# controller.net
KiCad netlist of a schematic drawn in EAGLE
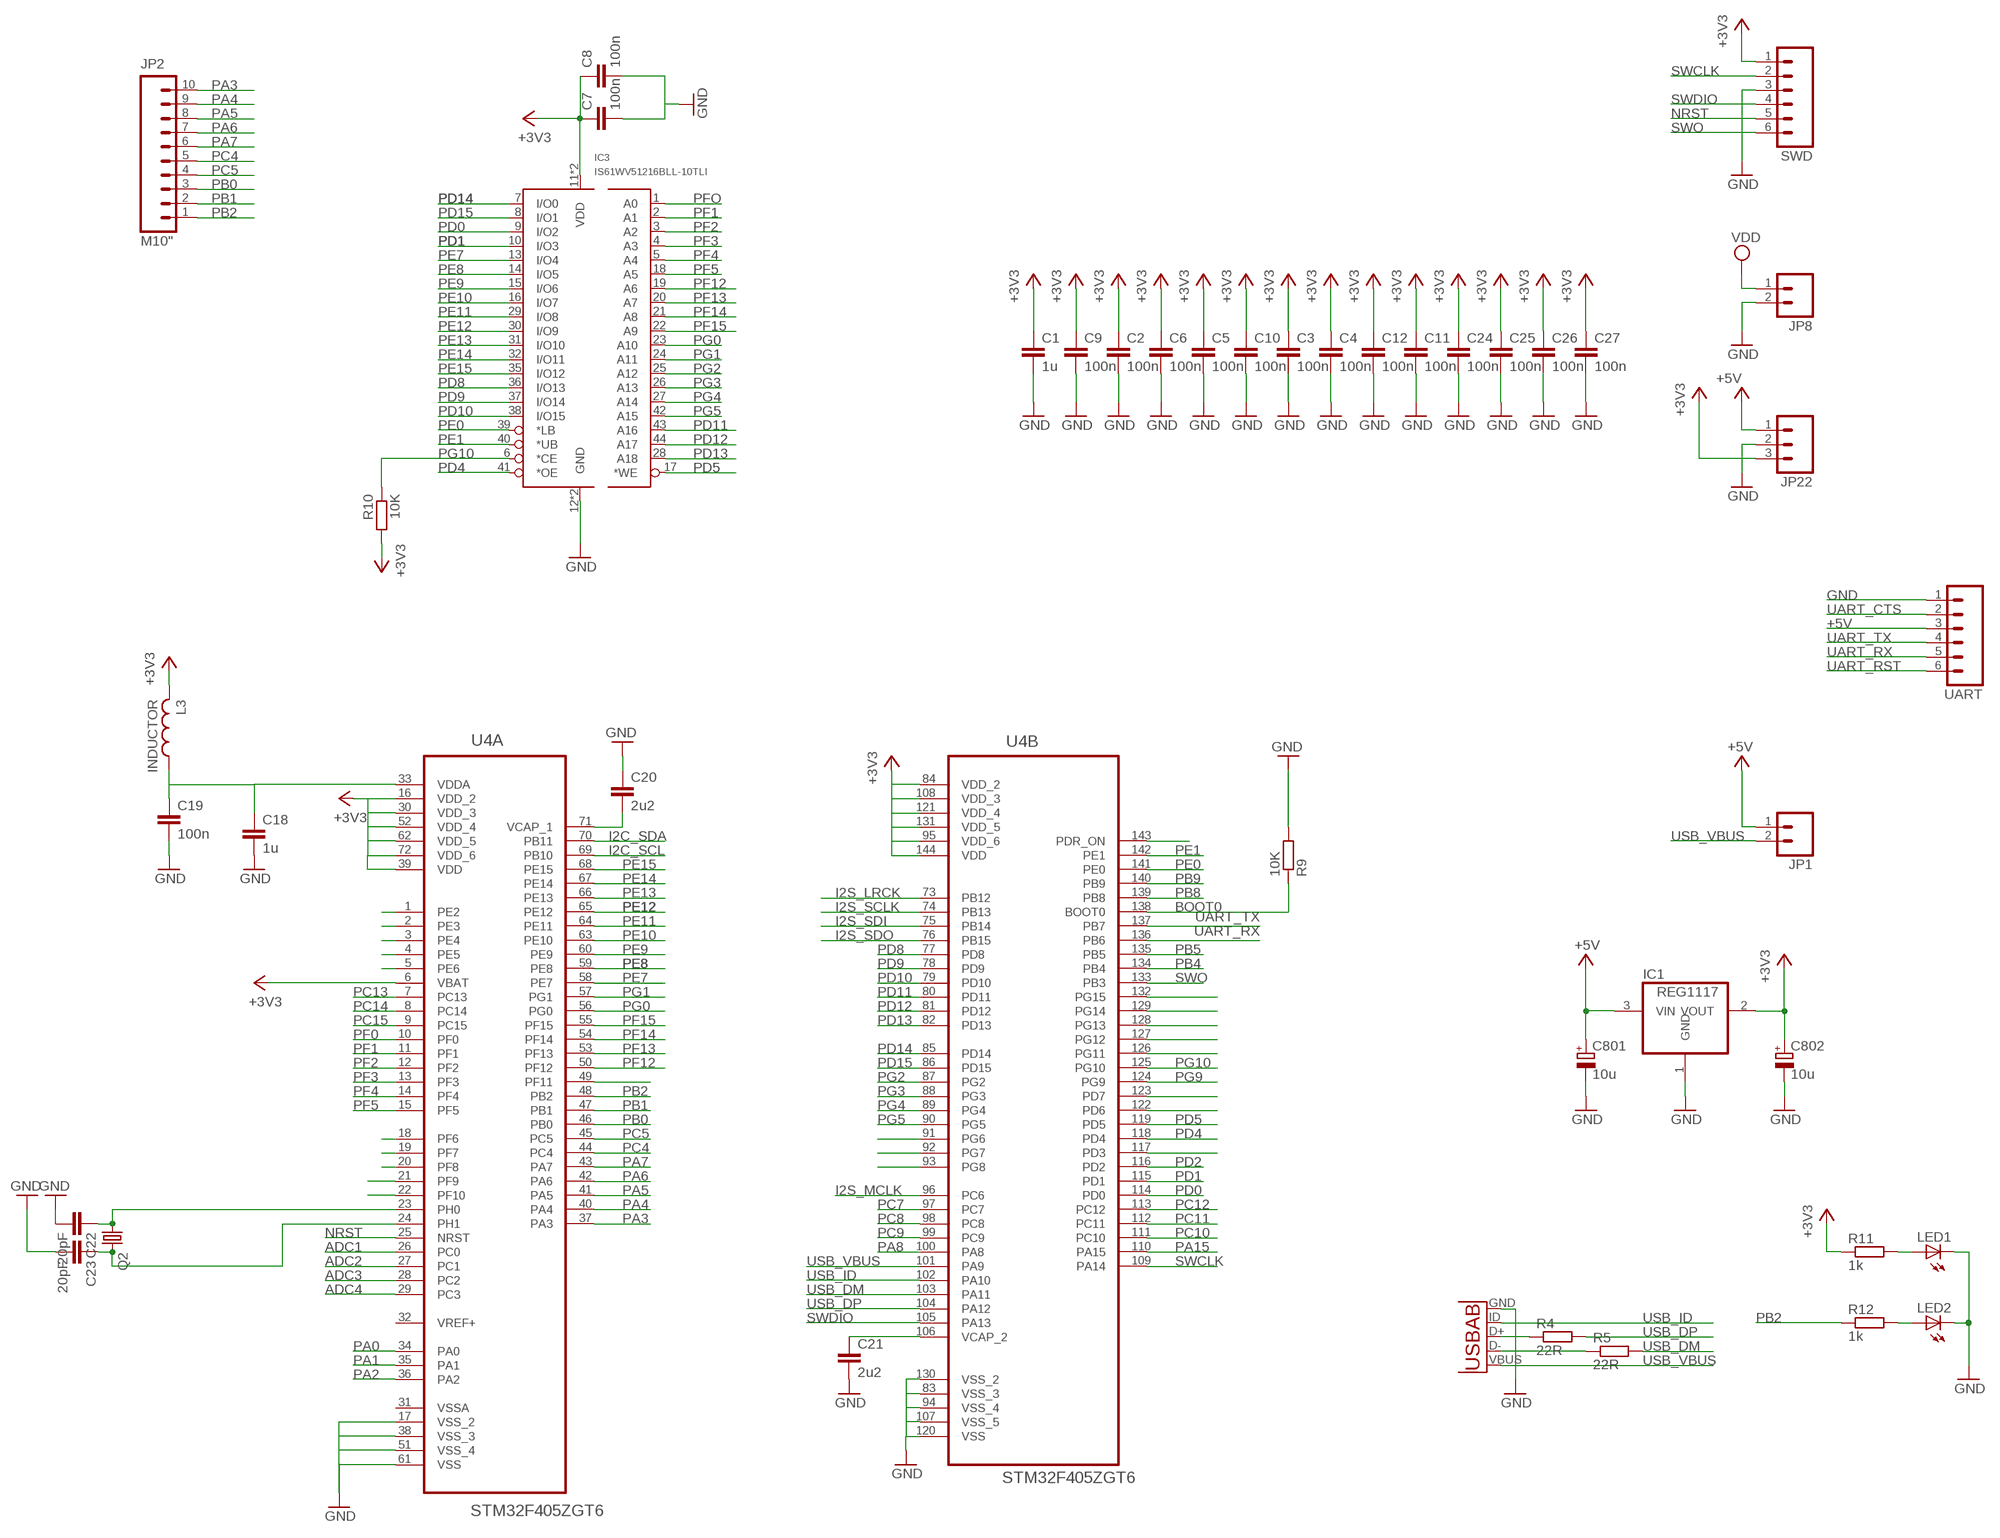
[diagram p0: schematic, sheet 1]

(export (version "E")
  (design (tool "Eeschema 10.0.6"))
  (components
    (comp (ref "C1")
      (value "1u")
      (footprint "eagle-import:C0603")
      (libsource (lib "eagle-import") (part "C-EUC0603"))
    )
    (comp (ref "C2")
      (value "100n")
      (footprint "eagle-import:C0603")
      (libsource (lib "eagle-import") (part "C-EUC0603"))
    )
    (comp (ref "C3")
      (value "100n")
      (footprint "eagle-import:C0603")
      (libsource (lib "eagle-import") (part "C-EUC0603"))
    )
    (comp (ref "C4")
      (value "100n")
      (footprint "eagle-import:C0603")
      (libsource (lib "eagle-import") (part "C-EUC0603"))
    )
    (comp (ref "C5")
      (value "100n")
      (footprint "eagle-import:C0603")
      (libsource (lib "eagle-import") (part "C-EUC0603"))
    )
    (comp (ref "C6")
      (value "100n")
      (footprint "eagle-import:C0603")
      (libsource (lib "eagle-import") (part "C-EUC0603"))
    )
    (comp (ref "C7")
      (value "100n")
      (footprint "eagle-import:C0603")
      (libsource (lib "eagle-import") (part "C-EUC0603"))
    )
    (comp (ref "C8")
      (value "100n")
      (footprint "eagle-import:C0603")
      (libsource (lib "eagle-import") (part "C-EUC0603"))
    )
    (comp (ref "C9")
      (value "100n")
      (footprint "eagle-import:C0603")
      (libsource (lib "eagle-import") (part "C-EUC0603"))
    )
    (comp (ref "C10")
      (value "100n")
      (footprint "eagle-import:C0603")
      (libsource (lib "eagle-import") (part "C-EUC0603"))
    )
    (comp (ref "C11")
      (value "100n")
      (footprint "eagle-import:C0603")
      (libsource (lib "eagle-import") (part "C-EUC0603"))
    )
    (comp (ref "C12")
      (value "100n")
      (footprint "eagle-import:C0603")
      (libsource (lib "eagle-import") (part "C-EUC0603"))
    )
    (comp (ref "C18")
      (value "1u")
      (footprint "eagle-import:C0603")
      (libsource (lib "eagle-import") (part "C-EUC0603"))
    )
    (comp (ref "C19")
      (value "100n")
      (footprint "eagle-import:C0603")
      (libsource (lib "eagle-import") (part "C-EUC0603"))
    )
    (comp (ref "C20")
      (value "2u2")
      (footprint "eagle-import:C0603")
      (libsource (lib "eagle-import") (part "C-EUC0603"))
    )
    (comp (ref "C21")
      (value "2u2")
      (footprint "eagle-import:C0603")
      (libsource (lib "eagle-import") (part "C-EUC0603"))
    )
    (comp (ref "C22")
      (value "20pF")
      (footprint "eagle-import:C0603")
      (libsource (lib "eagle-import") (part "C-EUC0603"))
    )
    (comp (ref "C23")
      (value "20pF")
      (footprint "eagle-import:C0603")
      (libsource (lib "eagle-import") (part "C-EUC0603"))
    )
    (comp (ref "C24")
      (value "100n")
      (footprint "eagle-import:C0603")
      (libsource (lib "eagle-import") (part "C-EUC0603"))
    )
    (comp (ref "C25")
      (value "100n")
      (footprint "eagle-import:C0603")
      (libsource (lib "eagle-import") (part "C-EUC0603"))
    )
    (comp (ref "C26")
      (value "100n")
      (footprint "eagle-import:C0603")
      (libsource (lib "eagle-import") (part "C-EUC0603"))
    )
    (comp (ref "C27")
      (value "100n")
      (footprint "eagle-import:C0603")
      (libsource (lib "eagle-import") (part "C-EUC0603"))
    )
    (comp (ref "C801")
      (value "10u")
      (footprint "eagle-import:PANASONIC_A")
      (libsource (lib "eagle-import") (part "CPOL-EUA"))
    )
    (comp (ref "C802")
      (value "10u")
      (footprint "eagle-import:PANASONIC_A")
      (libsource (lib "eagle-import") (part "CPOL-EUA"))
    )
    (comp (ref "IC1")
      (value "REG1117")
      (footprint "eagle-import:SOT223")
      (libsource (lib "eagle-import") (part "REG1117"))
    )
    (comp (ref "IC3")
      (value "IS61WV51216BLL-10TLI")
      (footprint "eagle-import:TSOP44-II")
      (libsource (lib "eagle-import") (part "IS61WV51216BLL-10TLI"))
    )
    (comp (ref "JP1")
      (value "M02PTH")
      (footprint "eagle-import:1X02")
      (libsource (lib "eagle-import") (part "M02PTH"))
    )
    (comp (ref "JP2")
      (value "M10\"")
      (footprint "eagle-import:1X10")
      (libsource (lib "eagle-import") (part "M10{dblquote}"))
    )
    (comp (ref "JP8")
      (value "M02PTH")
      (footprint "eagle-import:1X02")
      (libsource (lib "eagle-import") (part "M02PTH"))
    )
    (comp (ref "JP22")
      (value "M03PTH")
      (footprint "eagle-import:1X03")
      (libsource (lib "eagle-import") (part "M03PTH"))
    )
    (comp (ref "L3")
      (value "INDUCTOR")
      (footprint "eagle-import:0603")
      (libsource (lib "eagle-import") (part "INDUCTOR"))
    )
    (comp (ref "LED1")
      (value "LED1206")
      (footprint "eagle-import:LED-1206")
      (libsource (lib "eagle-import") (part "LED1206"))
    )
    (comp (ref "LED2")
      (value "LED1206")
      (footprint "eagle-import:LED-1206")
      (libsource (lib "eagle-import") (part "LED1206"))
    )
    (comp (ref "Q2")
      (value "CRYSTALHC49UP")
      (footprint "eagle-import:HC49UP")
      (libsource (lib "eagle-import") (part "CRYSTALHC49UP"))
    )
    (comp (ref "R4")
      (value "22R")
      (footprint "eagle-import:R0603")
      (libsource (lib "eagle-import") (part "R-EU_R0603"))
    )
    (comp (ref "R5")
      (value "22R")
      (footprint "eagle-import:R0603")
      (libsource (lib "eagle-import") (part "R-EU_R0603"))
    )
    (comp (ref "R9")
      (value "10K")
      (footprint "eagle-import:R0603")
      (libsource (lib "eagle-import") (part "R-EU_R0603"))
    )
    (comp (ref "R10")
      (value "10K")
      (footprint "eagle-import:R0603")
      (libsource (lib "eagle-import") (part "R-EU_R0603"))
    )
    (comp (ref "R11")
      (value "1k")
      (footprint "eagle-import:R0603")
      (libsource (lib "eagle-import") (part "R-EU_R0603"))
    )
    (comp (ref "R12")
      (value "1k")
      (footprint "eagle-import:R0603")
      (libsource (lib "eagle-import") (part "R-EU_R0603"))
    )
    (comp (ref "SWD")
      (value "M06SIP")
      (footprint "eagle-import:1X06")
      (libsource (lib "eagle-import") (part "M06SIP"))
    )
    (comp (ref "U3")
      (value "USB-AB")
      (footprint "eagle-import:USB-AB-MICRO-SMD")
      (libsource (lib "eagle-import") (part "USB-AB"))
    )
    (comp (ref "U4")
      (value "STM32F405ZGT6")
      (footprint "eagle-import:QFP50P2200X2200X160-144N")
      (libsource (lib "eagle-import") (part "STM32F405ZGT6"))
    )
    (comp (ref "UART")
      (value "M06SIP")
      (footprint "eagle-import:1X06")
      (libsource (lib "eagle-import") (part "M06SIP"))
    )
  )
  (nets
    (net (code "1") (name "+3V3") (class "Default")
      (node (ref "C1") (pin "1") (pinfunction "1_1") (pintype "passive"))
      (node (ref "C10") (pin "1") (pinfunction "1_1") (pintype "passive"))
      (node (ref "C11") (pin "1") (pinfunction "1_1") (pintype "passive"))
      (node (ref "C12") (pin "1") (pinfunction "1_1") (pintype "passive"))
      (node (ref "C2") (pin "1") (pinfunction "1_1") (pintype "passive"))
      (node (ref "C24") (pin "1") (pinfunction "1_1") (pintype "passive"))
      (node (ref "C25") (pin "1") (pinfunction "1_1") (pintype "passive"))
      (node (ref "C26") (pin "1") (pinfunction "1_1") (pintype "passive"))
      (node (ref "C27") (pin "1") (pinfunction "1_1") (pintype "passive"))
      (node (ref "C3") (pin "1") (pinfunction "1_1") (pintype "passive"))
      (node (ref "C4") (pin "1") (pinfunction "1_1") (pintype "passive"))
      (node (ref "C5") (pin "1") (pinfunction "1_1") (pintype "passive"))
      (node (ref "C6") (pin "1") (pinfunction "1_1") (pintype "passive"))
      (node (ref "C7") (pin "1") (pinfunction "1_1") (pintype "passive"))
      (node (ref "C8") (pin "1") (pinfunction "1_1") (pintype "passive"))
      (node (ref "C802") (pin "+") (pinfunction "+_+") (pintype "passive"))
      (node (ref "C9") (pin "1") (pinfunction "1_1") (pintype "passive"))
      (node (ref "IC1") (pin "2") (pinfunction "VOUT_2") (pintype "output"))
      (node (ref "IC3") (pin "11") (pinfunction "VDD_11") (pintype "power_in"))
      (node (ref "IC3") (pin "33") (pinfunction "VDD_33") (pintype "power_in"))
      (node (ref "JP22") (pin "3") (pinfunction "3_3") (pintype "passive"))
      (node (ref "L3") (pin "2") (pinfunction "2_2") (pintype "passive"))
      (node (ref "R10") (pin "2") (pinfunction "2_2") (pintype "passive"))
      (node (ref "R11") (pin "1") (pinfunction "1_1") (pintype "passive"))
      (node (ref "SWD") (pin "1") (pinfunction "1_1") (pintype "passive"))
      (node (ref "U4") (pin "108") (pinfunction "VDD_3_108") (pintype "power_in"))
      (node (ref "U4") (pin "121") (pinfunction "VDD_4_121") (pintype "power_in"))
      (node (ref "U4") (pin "131") (pinfunction "VDD_5_131") (pintype "power_in"))
      (node (ref "U4") (pin "144") (pinfunction "VDD_144") (pintype "power_in"))
      (node (ref "U4") (pin "16") (pinfunction "VDD_2_16") (pintype "power_in"))
      (node (ref "U4") (pin "30") (pinfunction "VDD_3_30") (pintype "power_in"))
      (node (ref "U4") (pin "39") (pinfunction "VDD_39") (pintype "power_in"))
      (node (ref "U4") (pin "52") (pinfunction "VDD_4_52") (pintype "power_in"))
      (node (ref "U4") (pin "6") (pinfunction "VBAT_6") (pintype "passive"))
      (node (ref "U4") (pin "62") (pinfunction "VDD_5_62") (pintype "power_in"))
      (node (ref "U4") (pin "72") (pinfunction "VDD_6_72") (pintype "power_in"))
      (node (ref "U4") (pin "84") (pinfunction "VDD_2_84") (pintype "power_in"))
      (node (ref "U4") (pin "95") (pinfunction "VDD_6_95") (pintype "power_in"))
    )
    (net (code "2") (name "+5V") (class "Default")
      (node (ref "C801") (pin "+") (pinfunction "+_+") (pintype "passive"))
      (node (ref "IC1") (pin "3") (pinfunction "VIN_3") (pintype "input"))
      (node (ref "JP1") (pin "1") (pinfunction "1_1") (pintype "passive"))
      (node (ref "JP22") (pin "1") (pinfunction "1_1") (pintype "passive"))
      (node (ref "UART") (pin "3") (pinfunction "3_3") (pintype "passive"))
    )
    (net (code "3") (name "/ADC1") (class "Default")
      (node (ref "U4") (pin "26") (pinfunction "PC0_26") (pintype "bidirectional"))
    )
    (net (code "4") (name "/ADC2") (class "Default")
      (node (ref "U4") (pin "27") (pinfunction "PC1_27") (pintype "bidirectional"))
    )
    (net (code "5") (name "/ADC3") (class "Default")
      (node (ref "U4") (pin "28") (pinfunction "PC2_28") (pintype "bidirectional"))
    )
    (net (code "6") (name "/ADC4") (class "Default")
      (node (ref "U4") (pin "29") (pinfunction "PC3_29") (pintype "bidirectional"))
    )
    (net (code "7") (name "/BOOT0") (class "Default")
      (node (ref "R9") (pin "1") (pinfunction "1_1") (pintype "passive"))
      (node (ref "U4") (pin "138") (pinfunction "BOOT0_138") (pintype "passive"))
    )
    (net (code "8") (name "/I2C_SCL") (class "Default")
      (node (ref "U4") (pin "69") (pinfunction "PB10_69") (pintype "bidirectional"))
    )
    (net (code "9") (name "/I2C_SDA") (class "Default")
      (node (ref "U4") (pin "70") (pinfunction "PB11_70") (pintype "bidirectional"))
    )
    (net (code "10") (name "/I2S_LRCK") (class "Default")
      (node (ref "U4") (pin "73") (pinfunction "PB12_73") (pintype "bidirectional"))
    )
    (net (code "11") (name "/I2S_MCLK") (class "Default")
      (node (ref "U4") (pin "96") (pinfunction "PC6_96") (pintype "bidirectional"))
    )
    (net (code "12") (name "/I2S_SCLK") (class "Default")
      (node (ref "U4") (pin "74") (pinfunction "PB13_74") (pintype "bidirectional"))
    )
    (net (code "13") (name "/I2S_SDI") (class "Default")
      (node (ref "U4") (pin "75") (pinfunction "PB14_75") (pintype "bidirectional"))
    )
    (net (code "14") (name "/I2S_SDO") (class "Default")
      (node (ref "U4") (pin "76") (pinfunction "PB15_76") (pintype "bidirectional"))
    )
    (net (code "15") (name "/NRST") (class "Default")
      (node (ref "SWD") (pin "5") (pinfunction "5_5") (pintype "passive"))
      (node (ref "U4") (pin "25") (pinfunction "NRST_25") (pintype "passive"))
    )
    (net (code "16") (name "/PA0") (class "Default")
      (node (ref "U4") (pin "34") (pinfunction "PA0_34") (pintype "bidirectional"))
    )
    (net (code "17") (name "/PA1") (class "Default")
      (node (ref "U4") (pin "35") (pinfunction "PA1_35") (pintype "bidirectional"))
    )
    (net (code "18") (name "/PA2") (class "Default")
      (node (ref "U4") (pin "36") (pinfunction "PA2_36") (pintype "bidirectional"))
    )
    (net (code "19") (name "/PA3") (class "Default")
      (node (ref "JP2") (pin "10") (pinfunction "10_10") (pintype "passive"))
      (node (ref "U4") (pin "37") (pinfunction "PA3_37") (pintype "bidirectional"))
    )
    (net (code "20") (name "/PA4") (class "Default")
      (node (ref "JP2") (pin "9") (pinfunction "9_9") (pintype "passive"))
      (node (ref "U4") (pin "40") (pinfunction "PA4_40") (pintype "bidirectional"))
    )
    (net (code "21") (name "/PA5") (class "Default")
      (node (ref "JP2") (pin "8") (pinfunction "8_8") (pintype "passive"))
      (node (ref "U4") (pin "41") (pinfunction "PA5_41") (pintype "bidirectional"))
    )
    (net (code "22") (name "/PA6") (class "Default")
      (node (ref "JP2") (pin "7") (pinfunction "7_7") (pintype "passive"))
      (node (ref "U4") (pin "42") (pinfunction "PA6_42") (pintype "bidirectional"))
    )
    (net (code "23") (name "/PA7") (class "Default")
      (node (ref "JP2") (pin "6") (pinfunction "6_6") (pintype "passive"))
      (node (ref "U4") (pin "43") (pinfunction "PA7_43") (pintype "bidirectional"))
    )
    (net (code "24") (name "/PA8") (class "Default")
      (node (ref "U4") (pin "100") (pinfunction "PA8_100") (pintype "bidirectional"))
    )
    (net (code "25") (name "/PA15") (class "Default")
      (node (ref "U4") (pin "110") (pinfunction "PA15_110") (pintype "bidirectional"))
    )
    (net (code "26") (name "/PB0") (class "Default")
      (node (ref "JP2") (pin "3") (pinfunction "3_3") (pintype "passive"))
      (node (ref "U4") (pin "46") (pinfunction "PB0_46") (pintype "bidirectional"))
    )
    (net (code "27") (name "/PB1") (class "Default")
      (node (ref "JP2") (pin "2") (pinfunction "2_2") (pintype "passive"))
      (node (ref "U4") (pin "47") (pinfunction "PB1_47") (pintype "bidirectional"))
    )
    (net (code "28") (name "/PB2") (class "Default")
      (node (ref "JP2") (pin "1") (pinfunction "1_1") (pintype "passive"))
      (node (ref "R12") (pin "1") (pinfunction "1_1") (pintype "passive"))
      (node (ref "U4") (pin "48") (pinfunction "PB2_48") (pintype "bidirectional"))
    )
    (net (code "29") (name "/PB4") (class "Default")
      (node (ref "U4") (pin "134") (pinfunction "PB4_134") (pintype "bidirectional"))
    )
    (net (code "30") (name "/PB5") (class "Default")
      (node (ref "U4") (pin "135") (pinfunction "PB5_135") (pintype "bidirectional"))
    )
    (net (code "31") (name "/PB8") (class "Default")
      (node (ref "U4") (pin "139") (pinfunction "PB8_139") (pintype "bidirectional"))
    )
    (net (code "32") (name "/PB9") (class "Default")
      (node (ref "U4") (pin "140") (pinfunction "PB9_140") (pintype "bidirectional"))
    )
    (net (code "33") (name "/PC4") (class "Default")
      (node (ref "JP2") (pin "5") (pinfunction "5_5") (pintype "passive"))
      (node (ref "U4") (pin "44") (pinfunction "PC4_44") (pintype "bidirectional"))
    )
    (net (code "34") (name "/PC5") (class "Default")
      (node (ref "JP2") (pin "4") (pinfunction "4_4") (pintype "passive"))
      (node (ref "U4") (pin "45") (pinfunction "PC5_45") (pintype "bidirectional"))
    )
    (net (code "35") (name "/PC7") (class "Default")
      (node (ref "U4") (pin "97") (pinfunction "PC7_97") (pintype "bidirectional"))
    )
    (net (code "36") (name "/PC8") (class "Default")
      (node (ref "U4") (pin "98") (pinfunction "PC8_98") (pintype "bidirectional"))
    )
    (net (code "37") (name "/PC9") (class "Default")
      (node (ref "U4") (pin "99") (pinfunction "PC9_99") (pintype "bidirectional"))
    )
    (net (code "38") (name "/PC10") (class "Default")
      (node (ref "U4") (pin "111") (pinfunction "PC10_111") (pintype "bidirectional"))
    )
    (net (code "39") (name "/PC11") (class "Default")
      (node (ref "U4") (pin "112") (pinfunction "PC11_112") (pintype "bidirectional"))
    )
    (net (code "40") (name "/PC12") (class "Default")
      (node (ref "U4") (pin "113") (pinfunction "PC12_113") (pintype "bidirectional"))
    )
    (net (code "41") (name "/PC13") (class "Default")
      (node (ref "U4") (pin "7") (pinfunction "PC13_7") (pintype "bidirectional"))
    )
    (net (code "42") (name "/PC14") (class "Default")
      (node (ref "U4") (pin "8") (pinfunction "PC14_8") (pintype "bidirectional"))
    )
    (net (code "43") (name "/PC15") (class "Default")
      (node (ref "U4") (pin "9") (pinfunction "PC15_9") (pintype "bidirectional"))
    )
    (net (code "44") (name "/PD0") (class "Default")
      (node (ref "IC3") (pin "9") (pinfunction "I/O2_9") (pintype "bidirectional"))
      (node (ref "U4") (pin "114") (pinfunction "PD0_114") (pintype "bidirectional"))
    )
    (net (code "45") (name "/PD1") (class "Default")
      (node (ref "IC3") (pin "10") (pinfunction "I/O3_10") (pintype "bidirectional"))
      (node (ref "U4") (pin "115") (pinfunction "PD1_115") (pintype "bidirectional"))
    )
    (net (code "46") (name "/PD2") (class "Default")
      (node (ref "U4") (pin "116") (pinfunction "PD2_116") (pintype "bidirectional"))
    )
    (net (code "47") (name "/PD4") (class "Default")
      (node (ref "IC3") (pin "41") (pinfunction "*OE_41") (pintype "bidirectional"))
      (node (ref "U4") (pin "118") (pinfunction "PD4_118") (pintype "bidirectional"))
    )
    (net (code "48") (name "/PD5") (class "Default")
      (node (ref "IC3") (pin "17") (pinfunction "*WE_17") (pintype "bidirectional"))
      (node (ref "U4") (pin "119") (pinfunction "PD5_119") (pintype "bidirectional"))
    )
    (net (code "49") (name "/PD8") (class "Default")
      (node (ref "IC3") (pin "36") (pinfunction "I/O13_36") (pintype "bidirectional"))
      (node (ref "U4") (pin "77") (pinfunction "PD8_77") (pintype "bidirectional"))
    )
    (net (code "50") (name "/PD9") (class "Default")
      (node (ref "IC3") (pin "37") (pinfunction "I/O14_37") (pintype "bidirectional"))
      (node (ref "U4") (pin "78") (pinfunction "PD9_78") (pintype "bidirectional"))
    )
    (net (code "51") (name "/PD10") (class "Default")
      (node (ref "IC3") (pin "38") (pinfunction "I/O15_38") (pintype "bidirectional"))
      (node (ref "U4") (pin "79") (pinfunction "PD10_79") (pintype "bidirectional"))
    )
    (net (code "52") (name "/PD11") (class "Default")
      (node (ref "IC3") (pin "43") (pinfunction "A16_43") (pintype "input"))
      (node (ref "U4") (pin "80") (pinfunction "PD11_80") (pintype "bidirectional"))
    )
    (net (code "53") (name "/PD12") (class "Default")
      (node (ref "IC3") (pin "44") (pinfunction "A17_44") (pintype "input"))
      (node (ref "U4") (pin "81") (pinfunction "PD12_81") (pintype "bidirectional"))
    )
    (net (code "54") (name "/PD13") (class "Default")
      (node (ref "IC3") (pin "28") (pinfunction "A18_28") (pintype "input"))
      (node (ref "U4") (pin "82") (pinfunction "PD13_82") (pintype "bidirectional"))
    )
    (net (code "55") (name "/PD14") (class "Default")
      (node (ref "IC3") (pin "7") (pinfunction "I/O0_7") (pintype "bidirectional"))
      (node (ref "U4") (pin "85") (pinfunction "PD14_85") (pintype "bidirectional"))
    )
    (net (code "56") (name "/PD15") (class "Default")
      (node (ref "IC3") (pin "8") (pinfunction "I/O1_8") (pintype "bidirectional"))
      (node (ref "U4") (pin "86") (pinfunction "PD15_86") (pintype "bidirectional"))
    )
    (net (code "57") (name "/PE0") (class "Default")
      (node (ref "IC3") (pin "39") (pinfunction "*LB_39") (pintype "bidirectional"))
      (node (ref "U4") (pin "141") (pinfunction "PE0_141") (pintype "bidirectional"))
    )
    (net (code "58") (name "/PE1") (class "Default")
      (node (ref "IC3") (pin "40") (pinfunction "*UB_40") (pintype "bidirectional"))
      (node (ref "U4") (pin "142") (pinfunction "PE1_142") (pintype "bidirectional"))
    )
    (net (code "59") (name "/PE7") (class "Default")
      (node (ref "IC3") (pin "13") (pinfunction "I/O4_13") (pintype "bidirectional"))
      (node (ref "U4") (pin "58") (pinfunction "PE7_58") (pintype "bidirectional"))
    )
    (net (code "60") (name "/PE8") (class "Default")
      (node (ref "IC3") (pin "14") (pinfunction "I/O5_14") (pintype "bidirectional"))
      (node (ref "U4") (pin "59") (pinfunction "PE8_59") (pintype "bidirectional"))
    )
    (net (code "61") (name "/PE9") (class "Default")
      (node (ref "IC3") (pin "15") (pinfunction "I/O6_15") (pintype "bidirectional"))
      (node (ref "U4") (pin "60") (pinfunction "PE9_60") (pintype "bidirectional"))
    )
    (net (code "62") (name "/PE10") (class "Default")
      (node (ref "IC3") (pin "16") (pinfunction "I/O7_16") (pintype "bidirectional"))
      (node (ref "U4") (pin "63") (pinfunction "PE10_63") (pintype "bidirectional"))
    )
    (net (code "63") (name "/PE11") (class "Default")
      (node (ref "IC3") (pin "29") (pinfunction "I/O8_29") (pintype "bidirectional"))
      (node (ref "U4") (pin "64") (pinfunction "PE11_64") (pintype "bidirectional"))
    )
    (net (code "64") (name "/PE12") (class "Default")
      (node (ref "IC3") (pin "30") (pinfunction "I/O9_30") (pintype "bidirectional"))
      (node (ref "U4") (pin "65") (pinfunction "PE12_65") (pintype "bidirectional"))
    )
    (net (code "65") (name "/PE13") (class "Default")
      (node (ref "IC3") (pin "31") (pinfunction "I/O10_31") (pintype "bidirectional"))
      (node (ref "U4") (pin "66") (pinfunction "PE13_66") (pintype "bidirectional"))
    )
    (net (code "66") (name "/PE14") (class "Default")
      (node (ref "IC3") (pin "32") (pinfunction "I/O11_32") (pintype "bidirectional"))
      (node (ref "U4") (pin "67") (pinfunction "PE14_67") (pintype "bidirectional"))
    )
    (net (code "67") (name "/PE15") (class "Default")
      (node (ref "IC3") (pin "35") (pinfunction "I/O12_35") (pintype "bidirectional"))
      (node (ref "U4") (pin "68") (pinfunction "PE15_68") (pintype "bidirectional"))
    )
    (net (code "68") (name "/PF0") (class "Default")
      (node (ref "U4") (pin "10") (pinfunction "PF0_10") (pintype "bidirectional"))
    )
    (net (code "69") (name "/PF1") (class "Default")
      (node (ref "IC3") (pin "2") (pinfunction "A1_2") (pintype "input"))
      (node (ref "U4") (pin "11") (pinfunction "PF1_11") (pintype "bidirectional"))
    )
    (net (code "70") (name "/PF2") (class "Default")
      (node (ref "IC3") (pin "3") (pinfunction "A2_3") (pintype "input"))
      (node (ref "U4") (pin "12") (pinfunction "PF2_12") (pintype "bidirectional"))
    )
    (net (code "71") (name "/PF3") (class "Default")
      (node (ref "IC3") (pin "4") (pinfunction "A3_4") (pintype "input"))
      (node (ref "U4") (pin "13") (pinfunction "PF3_13") (pintype "bidirectional"))
    )
    (net (code "72") (name "/PF4") (class "Default")
      (node (ref "IC3") (pin "5") (pinfunction "A4_5") (pintype "input"))
      (node (ref "U4") (pin "14") (pinfunction "PF4_14") (pintype "bidirectional"))
    )
    (net (code "73") (name "/PF5") (class "Default")
      (node (ref "IC3") (pin "18") (pinfunction "A5_18") (pintype "input"))
      (node (ref "U4") (pin "15") (pinfunction "PF5_15") (pintype "bidirectional"))
    )
    (net (code "74") (name "/PF12") (class "Default")
      (node (ref "IC3") (pin "19") (pinfunction "A6_19") (pintype "input"))
      (node (ref "U4") (pin "50") (pinfunction "PF12_50") (pintype "bidirectional"))
    )
    (net (code "75") (name "/PF13") (class "Default")
      (node (ref "IC3") (pin "20") (pinfunction "A7_20") (pintype "input"))
      (node (ref "U4") (pin "53") (pinfunction "PF13_53") (pintype "bidirectional"))
    )
    (net (code "76") (name "/PF14") (class "Default")
      (node (ref "IC3") (pin "21") (pinfunction "A8_21") (pintype "input"))
      (node (ref "U4") (pin "54") (pinfunction "PF14_54") (pintype "bidirectional"))
    )
    (net (code "77") (name "/PF15") (class "Default")
      (node (ref "IC3") (pin "22") (pinfunction "A9_22") (pintype "input"))
      (node (ref "U4") (pin "55") (pinfunction "PF15_55") (pintype "bidirectional"))
    )
    (net (code "78") (name "/PFO") (class "Default")
      (node (ref "IC3") (pin "1") (pinfunction "A0_1") (pintype "input"))
    )
    (net (code "79") (name "/PG0") (class "Default")
      (node (ref "IC3") (pin "23") (pinfunction "A10_23") (pintype "input"))
      (node (ref "U4") (pin "56") (pinfunction "PG0_56") (pintype "bidirectional"))
    )
    (net (code "80") (name "/PG1") (class "Default")
      (node (ref "IC3") (pin "24") (pinfunction "A11_24") (pintype "input"))
      (node (ref "U4") (pin "57") (pinfunction "PG1_57") (pintype "bidirectional"))
    )
    (net (code "81") (name "/PG2") (class "Default")
      (node (ref "IC3") (pin "25") (pinfunction "A12_25") (pintype "input"))
      (node (ref "U4") (pin "87") (pinfunction "PG2_87") (pintype "bidirectional"))
    )
    (net (code "82") (name "/PG3") (class "Default")
      (node (ref "IC3") (pin "26") (pinfunction "A13_26") (pintype "input"))
      (node (ref "U4") (pin "88") (pinfunction "PG3_88") (pintype "bidirectional"))
    )
    (net (code "83") (name "/PG4") (class "Default")
      (node (ref "IC3") (pin "27") (pinfunction "A14_27") (pintype "input"))
      (node (ref "U4") (pin "89") (pinfunction "PG4_89") (pintype "bidirectional"))
    )
    (net (code "84") (name "/PG5") (class "Default")
      (node (ref "IC3") (pin "42") (pinfunction "A15_42") (pintype "input"))
      (node (ref "U4") (pin "90") (pinfunction "PG5_90") (pintype "bidirectional"))
    )
    (net (code "85") (name "/PG9") (class "Default")
      (node (ref "U4") (pin "124") (pinfunction "PG9_124") (pintype "bidirectional"))
    )
    (net (code "86") (name "/PG10") (class "Default")
      (node (ref "IC3") (pin "6") (pinfunction "*CE_6") (pintype "bidirectional"))
      (node (ref "R10") (pin "1") (pinfunction "1_1") (pintype "passive"))
      (node (ref "U4") (pin "125") (pinfunction "PG10_125") (pintype "bidirectional"))
    )
    (net (code "87") (name "/SWCLK") (class "Default")
      (node (ref "SWD") (pin "2") (pinfunction "2_2") (pintype "passive"))
      (node (ref "U4") (pin "109") (pinfunction "PA14_109") (pintype "bidirectional"))
    )
    (net (code "88") (name "/SWDIO") (class "Default")
      (node (ref "SWD") (pin "4") (pinfunction "4_4") (pintype "passive"))
      (node (ref "U4") (pin "105") (pinfunction "PA13_105") (pintype "bidirectional"))
    )
    (net (code "89") (name "/SWO") (class "Default")
      (node (ref "SWD") (pin "6") (pinfunction "6_6") (pintype "passive"))
      (node (ref "U4") (pin "133") (pinfunction "PB3_133") (pintype "bidirectional"))
    )
    (net (code "90") (name "/UART_CTS") (class "Default")
      (node (ref "UART") (pin "2") (pinfunction "2_2") (pintype "passive"))
    )
    (net (code "91") (name "/UART_RST") (class "Default")
      (node (ref "UART") (pin "6") (pinfunction "6_6") (pintype "passive"))
    )
    (net (code "92") (name "/UART_RX") (class "Default")
      (node (ref "U4") (pin "136") (pinfunction "PB6_136") (pintype "bidirectional"))
      (node (ref "UART") (pin "5") (pinfunction "5_5") (pintype "passive"))
    )
    (net (code "93") (name "/UART_TX") (class "Default")
      (node (ref "U4") (pin "137") (pinfunction "PB7_137") (pintype "bidirectional"))
      (node (ref "UART") (pin "4") (pinfunction "4_4") (pintype "passive"))
    )
    (net (code "94") (name "/USB_DM") (class "Default")
      (node (ref "R5") (pin "2") (pinfunction "2_2") (pintype "passive"))
      (node (ref "U4") (pin "103") (pinfunction "PA11_103") (pintype "bidirectional"))
    )
    (net (code "95") (name "/USB_DP") (class "Default")
      (node (ref "R4") (pin "2") (pinfunction "2_2") (pintype "passive"))
      (node (ref "U4") (pin "104") (pinfunction "PA12_104") (pintype "bidirectional"))
    )
    (net (code "96") (name "/USB_ID") (class "Default")
      (node (ref "U3") (pin "ID") (pinfunction "USBID_ID") (pintype "bidirectional"))
      (node (ref "U4") (pin "102") (pinfunction "PA10_102") (pintype "bidirectional"))
    )
    (net (code "97") (name "/USB_VBUS") (class "Default")
      (node (ref "JP1") (pin "2") (pinfunction "2_2") (pintype "passive"))
      (node (ref "U3") (pin "VBUS") (pinfunction "VBUS_VBUS") (pintype "bidirectional"))
      (node (ref "U4") (pin "101") (pinfunction "PA9_101") (pintype "bidirectional"))
    )
    (net (code "98") (name "/VSSA") (class "Default")
      (node (ref "U4") (pin "31") (pinfunction "VSSA_31") (pintype "power_in"))
    )
    (net (code "99") (name "GND") (class "Default")
      (node (ref "C1") (pin "2") (pinfunction "2_2") (pintype "passive"))
      (node (ref "C10") (pin "2") (pinfunction "2_2") (pintype "passive"))
      (node (ref "C11") (pin "2") (pinfunction "2_2") (pintype "passive"))
      (node (ref "C12") (pin "2") (pinfunction "2_2") (pintype "passive"))
      (node (ref "C18") (pin "2") (pinfunction "2_2") (pintype "passive"))
      (node (ref "C19") (pin "2") (pinfunction "2_2") (pintype "passive"))
      (node (ref "C2") (pin "2") (pinfunction "2_2") (pintype "passive"))
      (node (ref "C20") (pin "1") (pinfunction "1_1") (pintype "passive"))
      (node (ref "C21") (pin "2") (pinfunction "2_2") (pintype "passive"))
      (node (ref "C22") (pin "2") (pinfunction "2_2") (pintype "passive"))
      (node (ref "C23") (pin "2") (pinfunction "2_2") (pintype "passive"))
      (node (ref "C24") (pin "2") (pinfunction "2_2") (pintype "passive"))
      (node (ref "C25") (pin "2") (pinfunction "2_2") (pintype "passive"))
      (node (ref "C26") (pin "2") (pinfunction "2_2") (pintype "passive"))
      (node (ref "C27") (pin "2") (pinfunction "2_2") (pintype "passive"))
      (node (ref "C3") (pin "2") (pinfunction "2_2") (pintype "passive"))
      (node (ref "C4") (pin "2") (pinfunction "2_2") (pintype "passive"))
      (node (ref "C5") (pin "2") (pinfunction "2_2") (pintype "passive"))
      (node (ref "C6") (pin "2") (pinfunction "2_2") (pintype "passive"))
      (node (ref "C7") (pin "2") (pinfunction "2_2") (pintype "passive"))
      (node (ref "C8") (pin "2") (pinfunction "2_2") (pintype "passive"))
      (node (ref "C801") (pin "-") (pinfunction "-_-") (pintype "passive"))
      (node (ref "C802") (pin "-") (pinfunction "-_-") (pintype "passive"))
      (node (ref "C9") (pin "2") (pinfunction "2_2") (pintype "passive"))
      (node (ref "IC1") (pin "1") (pinfunction "GND_1") (pintype "power_in"))
      (node (ref "IC3") (pin "12") (pinfunction "GND_12") (pintype "power_in"))
      (node (ref "IC3") (pin "34") (pinfunction "GND_34") (pintype "power_in"))
      (node (ref "JP22") (pin "2") (pinfunction "2_2") (pintype "passive"))
      (node (ref "JP8") (pin "2") (pinfunction "2_2") (pintype "passive"))
      (node (ref "LED1") (pin "C") (pinfunction "C_C") (pintype "passive"))
      (node (ref "LED2") (pin "C") (pinfunction "C_C") (pintype "passive"))
      (node (ref "R9") (pin "2") (pinfunction "2_2") (pintype "passive"))
      (node (ref "SWD") (pin "3") (pinfunction "3_3") (pintype "passive"))
      (node (ref "U3") (pin "GND") (pinfunction "GND_GND") (pintype "bidirectional"))
      (node (ref "U4") (pin "107") (pinfunction "VSS_5_107") (pintype "power_in"))
      (node (ref "U4") (pin "120") (pinfunction "VSS_120") (pintype "power_in"))
      (node (ref "U4") (pin "130") (pinfunction "VSS_2_130") (pintype "power_in"))
      (node (ref "U4") (pin "17") (pinfunction "VSS_2_17") (pintype "power_in"))
      (node (ref "U4") (pin "38") (pinfunction "VSS_3_38") (pintype "power_in"))
      (node (ref "U4") (pin "51") (pinfunction "VSS_4_51") (pintype "power_in"))
      (node (ref "U4") (pin "61") (pinfunction "VSS_61") (pintype "power_in"))
      (node (ref "U4") (pin "83") (pinfunction "VSS_3_83") (pintype "power_in"))
      (node (ref "U4") (pin "94") (pinfunction "VSS_4_94") (pintype "power_in"))
      (node (ref "UART") (pin "1") (pinfunction "1_1") (pintype "passive"))
    )
    (net (code "100") (name "Net-(LED1-PadA)") (class "Default")
      (node (ref "LED1") (pin "A") (pinfunction "A_A") (pintype "passive"))
      (node (ref "R11") (pin "2") (pinfunction "2_2") (pintype "passive"))
    )
    (net (code "101") (name "Net-(LED2-PadA)") (class "Default")
      (node (ref "LED2") (pin "A") (pinfunction "A_A") (pintype "passive"))
      (node (ref "R12") (pin "2") (pinfunction "2_2") (pintype "passive"))
    )
    (net (code "102") (name "Net-(R4-Pad1)") (class "Default")
      (node (ref "R4") (pin "1") (pinfunction "1_1") (pintype "passive"))
      (node (ref "U3") (pin "D+") (pinfunction "D+_D+") (pintype "bidirectional"))
    )
    (net (code "103") (name "Net-(R5-Pad1)") (class "Default")
      (node (ref "R5") (pin "1") (pinfunction "1_1") (pintype "passive"))
      (node (ref "U3") (pin "D-") (pinfunction "D-_D-") (pintype "bidirectional"))
    )
    (net (code "104") (name "Net-(U4A-PH0)") (class "Default")
      (node (ref "C22") (pin "1") (pinfunction "1_1") (pintype "passive"))
      (node (ref "Q2") (pin "1") (pinfunction "1_1") (pintype "passive"))
      (node (ref "U4") (pin "23") (pinfunction "PH0_23") (pintype "bidirectional"))
    )
    (net (code "105") (name "Net-(U4A-PH1)") (class "Default")
      (node (ref "C23") (pin "1") (pinfunction "1_1") (pintype "passive"))
      (node (ref "Q2") (pin "2") (pinfunction "2_2") (pintype "passive"))
      (node (ref "U4") (pin "24") (pinfunction "PH1_24") (pintype "bidirectional"))
    )
    (net (code "106") (name "Net-(U4A-VCAP_1)") (class "Default")
      (node (ref "C20") (pin "2") (pinfunction "2_2") (pintype "passive"))
      (node (ref "U4") (pin "71") (pinfunction "VCAP_1_71") (pintype "passive"))
    )
    (net (code "107") (name "Net-(U4A-VDDA)") (class "Default")
      (node (ref "C18") (pin "1") (pinfunction "1_1") (pintype "passive"))
      (node (ref "C19") (pin "1") (pinfunction "1_1") (pintype "passive"))
      (node (ref "L3") (pin "1") (pinfunction "1_1") (pintype "passive"))
      (node (ref "U4") (pin "33") (pinfunction "VDDA_33") (pintype "power_in"))
    )
    (net (code "108") (name "Net-(U4B-VCAP_2)") (class "Default")
      (node (ref "C21") (pin "1") (pinfunction "1_1") (pintype "passive"))
      (node (ref "U4") (pin "106") (pinfunction "VCAP_2_106") (pintype "passive"))
    )
    (net (code "109") (name "VDD") (class "Default")
      (node (ref "JP8") (pin "1") (pinfunction "1_1") (pintype "passive"))
    )
    (net (code "110") (name "unconnected-(U4A-PE2-Pad1)") (class "Default")
      (node (ref "U4") (pin "1") (pinfunction "PE2_1") (pintype "bidirectional"))
    )
    (net (code "111") (name "unconnected-(U4A-PE3-Pad2)") (class "Default")
      (node (ref "U4") (pin "2") (pinfunction "PE3_2") (pintype "bidirectional"))
    )
    (net (code "112") (name "unconnected-(U4A-PE4-Pad3)") (class "Default")
      (node (ref "U4") (pin "3") (pinfunction "PE4_3") (pintype "bidirectional"))
    )
    (net (code "113") (name "unconnected-(U4A-PE5-Pad4)") (class "Default")
      (node (ref "U4") (pin "4") (pinfunction "PE5_4") (pintype "bidirectional"))
    )
    (net (code "114") (name "unconnected-(U4A-PE6-Pad5)") (class "Default")
      (node (ref "U4") (pin "5") (pinfunction "PE6_5") (pintype "bidirectional"))
    )
    (net (code "115") (name "unconnected-(U4A-PF6-Pad18)") (class "Default")
      (node (ref "U4") (pin "18") (pinfunction "PF6_18") (pintype "bidirectional"))
    )
    (net (code "116") (name "unconnected-(U4A-PF7-Pad19)") (class "Default")
      (node (ref "U4") (pin "19") (pinfunction "PF7_19") (pintype "bidirectional"))
    )
    (net (code "117") (name "unconnected-(U4A-PF8-Pad20)") (class "Default")
      (node (ref "U4") (pin "20") (pinfunction "PF8_20") (pintype "bidirectional"))
    )
    (net (code "118") (name "unconnected-(U4A-PF9-Pad21)") (class "Default")
      (node (ref "U4") (pin "21") (pinfunction "PF9_21") (pintype "bidirectional"))
    )
    (net (code "119") (name "unconnected-(U4A-PF10-Pad22)") (class "Default")
      (node (ref "U4") (pin "22") (pinfunction "PF10_22") (pintype "bidirectional"))
    )
    (net (code "120") (name "unconnected-(U4A-PF11-Pad49)") (class "Default")
      (node (ref "U4") (pin "49") (pinfunction "PF11_49") (pintype "bidirectional"))
    )
    (net (code "121") (name "unconnected-(U4A-VREF+-Pad32)") (class "Default")
      (node (ref "U4") (pin "32") (pinfunction "VREF+_32") (pintype "passive"))
    )
    (net (code "122") (name "unconnected-(U4B-PD3-Pad117)") (class "Default")
      (node (ref "U4") (pin "117") (pinfunction "PD3_117") (pintype "bidirectional"))
    )
    (net (code "123") (name "unconnected-(U4B-PD6-Pad122)") (class "Default")
      (node (ref "U4") (pin "122") (pinfunction "PD6_122") (pintype "bidirectional"))
    )
    (net (code "124") (name "unconnected-(U4B-PD7-Pad123)") (class "Default")
      (node (ref "U4") (pin "123") (pinfunction "PD7_123") (pintype "bidirectional"))
    )
    (net (code "125") (name "unconnected-(U4B-PDR_ON-Pad143)") (class "Default")
      (node (ref "U4") (pin "143") (pinfunction "PDR_ON_143") (pintype "passive"))
    )
    (net (code "126") (name "unconnected-(U4B-PG6-Pad91)") (class "Default")
      (node (ref "U4") (pin "91") (pinfunction "PG6_91") (pintype "bidirectional"))
    )
    (net (code "127") (name "unconnected-(U4B-PG7-Pad92)") (class "Default")
      (node (ref "U4") (pin "92") (pinfunction "PG7_92") (pintype "bidirectional"))
    )
    (net (code "128") (name "unconnected-(U4B-PG8-Pad93)") (class "Default")
      (node (ref "U4") (pin "93") (pinfunction "PG8_93") (pintype "bidirectional"))
    )
    (net (code "129") (name "unconnected-(U4B-PG11-Pad126)") (class "Default")
      (node (ref "U4") (pin "126") (pinfunction "PG11_126") (pintype "bidirectional"))
    )
    (net (code "130") (name "unconnected-(U4B-PG12-Pad127)") (class "Default")
      (node (ref "U4") (pin "127") (pinfunction "PG12_127") (pintype "bidirectional"))
    )
    (net (code "131") (name "unconnected-(U4B-PG13-Pad128)") (class "Default")
      (node (ref "U4") (pin "128") (pinfunction "PG13_128") (pintype "bidirectional"))
    )
    (net (code "132") (name "unconnected-(U4B-PG14-Pad129)") (class "Default")
      (node (ref "U4") (pin "129") (pinfunction "PG14_129") (pintype "bidirectional"))
    )
    (net (code "133") (name "unconnected-(U4B-PG15-Pad132)") (class "Default")
      (node (ref "U4") (pin "132") (pinfunction "PG15_132") (pintype "bidirectional"))
    )
  )
)
